# MT3608_1A.net
KiCad netlist of a schematic drawn in Altium Designer
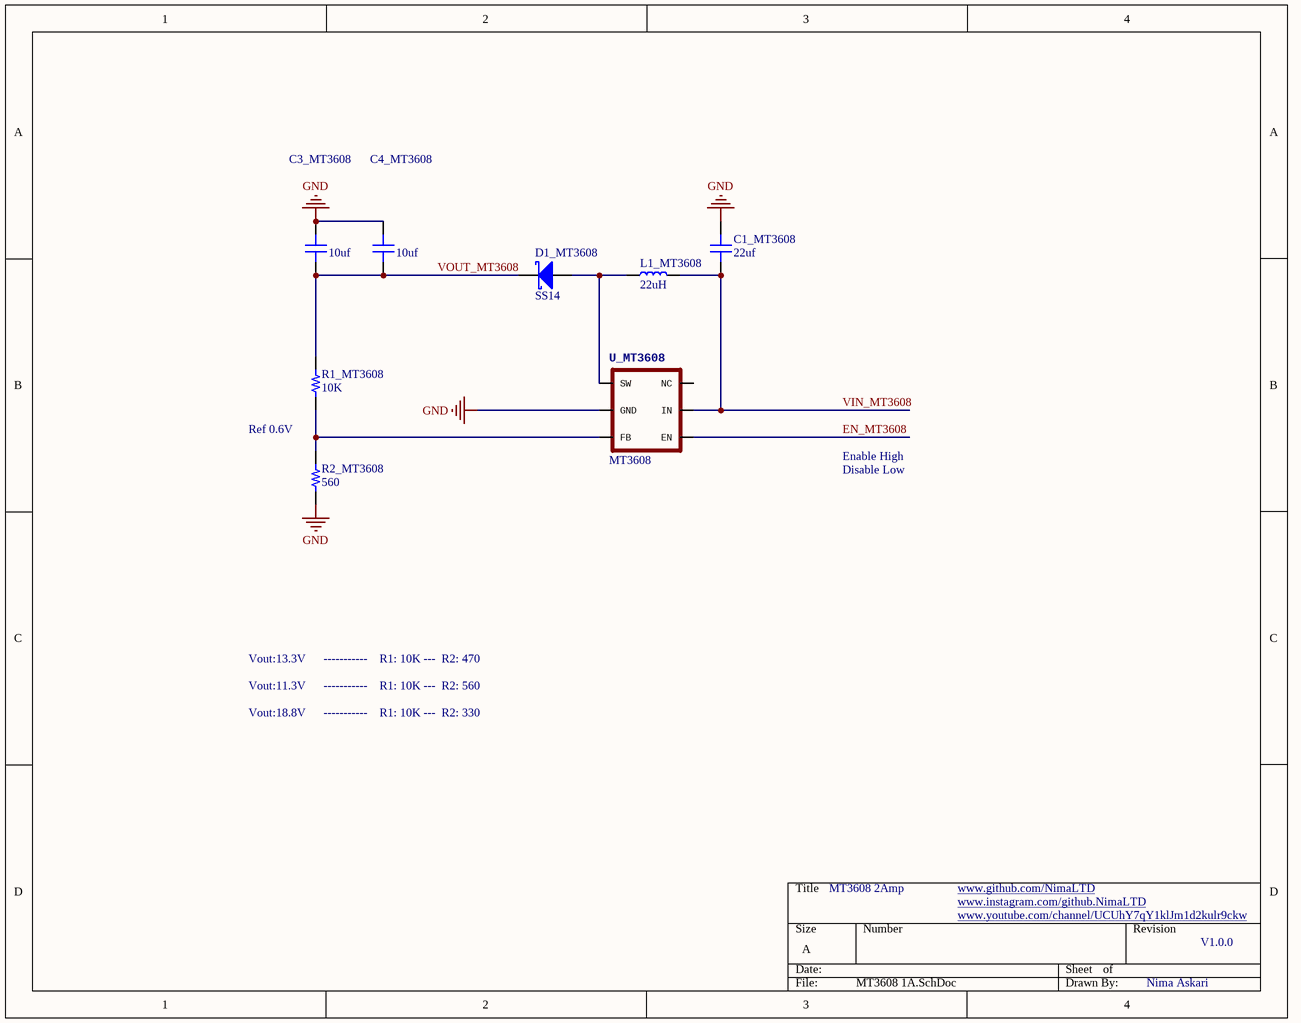
[diagram p0: MT3608 1A.SchDoc]

(export (version "E")
  (design (tool "Eeschema 10.0.6"))
  (components
    (comp (ref "C1_MT3608")
      (value "22uf")
      (footprint "CAP 1206")
      (description "SMT Capacitor")
      (libsource (lib "CAPACITOR") (part "Cap SMD 1206"))
    )
    (comp (ref "C3_MT3608")
      (value "10uf")
      (footprint "CAP 1206")
      (description "SMT Capacitor")
      (libsource (lib "CAPACITOR") (part "Cap SMD 1206"))
    )
    (comp (ref "C4_MT3608")
      (value "10uf")
      (footprint "CAP 1206")
      (description "SMT Capacitor")
      (libsource (lib "CAPACITOR") (part "Cap SMD 1206"))
    )
    (comp (ref "D1_MT3608")
      (value "SS14 SMD")
      (footprint "DO214AC SMA")
      (description "1A Schottky")
      (fields (field (name "PARAMETER 1") "SS14"))
      (libsource (lib "DIODE") (part "SS14 SMD"))
    )
    (comp (ref "L1_MT3608")
      (value "22uH")
      (footprint "IND 7X7")
      (description "SMT Inductor")
      (fields (field (name "Comment") "Inductor SMD POWER 7X7mm"))
      (libsource (lib "INDUCTOR") (part "Inductor SMD POWER 7X7mm"))
    )
    (comp (ref "R1_MT3608")
      (value "10K")
      (footprint "RES 0805")
      (description "SMD Resistor")
      (libsource (lib "RESISTOR") (part "Res SMD 0805"))
    )
    (comp (ref "R2_MT3608")
      (value "560")
      (footprint "RES 0805")
      (description "SMD Resistor")
      (libsource (lib "RESISTOR") (part "Res SMD 0805"))
    )
    (comp (ref "U_MT3608")
      (value "MT3608")
      (footprint "SOT23-6")
      (description "Boost")
      (fields (field (name "PARAMETER") "MT3608"))
      (libsource (lib "IC") (part "MT3608"))
    )
  )
  (nets
    (net (code "1") (name "/EN_MT3608") (class "Default")
      (node (ref "U_MT3608") (pin "4") (pinfunction "EN_4") (pintype "passive"))
    )
    (net (code "2") (name "/VIN_MT3608") (class "Default")
      (node (ref "C1_MT3608") (pin "1") (pinfunction "1_1") (pintype "passive"))
      (node (ref "L1_MT3608") (pin "2") (pinfunction "2_2") (pintype "passive"))
      (node (ref "U_MT3608") (pin "5") (pinfunction "IN_5") (pintype "passive"))
    )
    (net (code "3") (name "/VOUT_MT3608") (class "Default")
      (node (ref "C3_MT3608") (pin "1") (pinfunction "1_1") (pintype "passive"))
      (node (ref "C4_MT3608") (pin "1") (pinfunction "1_1") (pintype "passive"))
      (node (ref "D1_MT3608") (pin "2") (pinfunction "K_2") (pintype "passive"))
      (node (ref "R1_MT3608") (pin "2") (pinfunction "2_2") (pintype "passive"))
    )
    (net (code "4") (name "GND") (class "Default")
      (node (ref "C1_MT3608") (pin "2") (pinfunction "2_2") (pintype "passive"))
      (node (ref "C3_MT3608") (pin "2") (pinfunction "2_2") (pintype "passive"))
      (node (ref "C4_MT3608") (pin "2") (pinfunction "2_2") (pintype "passive"))
      (node (ref "R2_MT3608") (pin "1") (pinfunction "1_1") (pintype "passive"))
      (node (ref "U_MT3608") (pin "2") (pinfunction "GND_2") (pintype "passive"))
    )
    (net (code "5") (name "Net-(D1_MT3608-A)") (class "Default")
      (node (ref "D1_MT3608") (pin "1") (pinfunction "A_1") (pintype "passive"))
      (node (ref "L1_MT3608") (pin "1") (pinfunction "1_1") (pintype "passive"))
      (node (ref "U_MT3608") (pin "1") (pinfunction "SW_1") (pintype "passive"))
    )
    (net (code "6") (name "Net-(U_MT3608-FB)") (class "Default")
      (node (ref "R1_MT3608") (pin "1") (pinfunction "1_1") (pintype "passive"))
      (node (ref "R2_MT3608") (pin "2") (pinfunction "2_2") (pintype "passive"))
      (node (ref "U_MT3608") (pin "3") (pinfunction "FB_3") (pintype "passive"))
    )
    (net (code "7") (name "unconnected-(U_MT3608-NC-Pad6)") (class "Default")
      (node (ref "U_MT3608") (pin "6") (pinfunction "NC_6") (pintype "passive"))
    )
  )
)
